# 1_Interface.net
KiCad netlist of a schematic drawn in Altium Designer
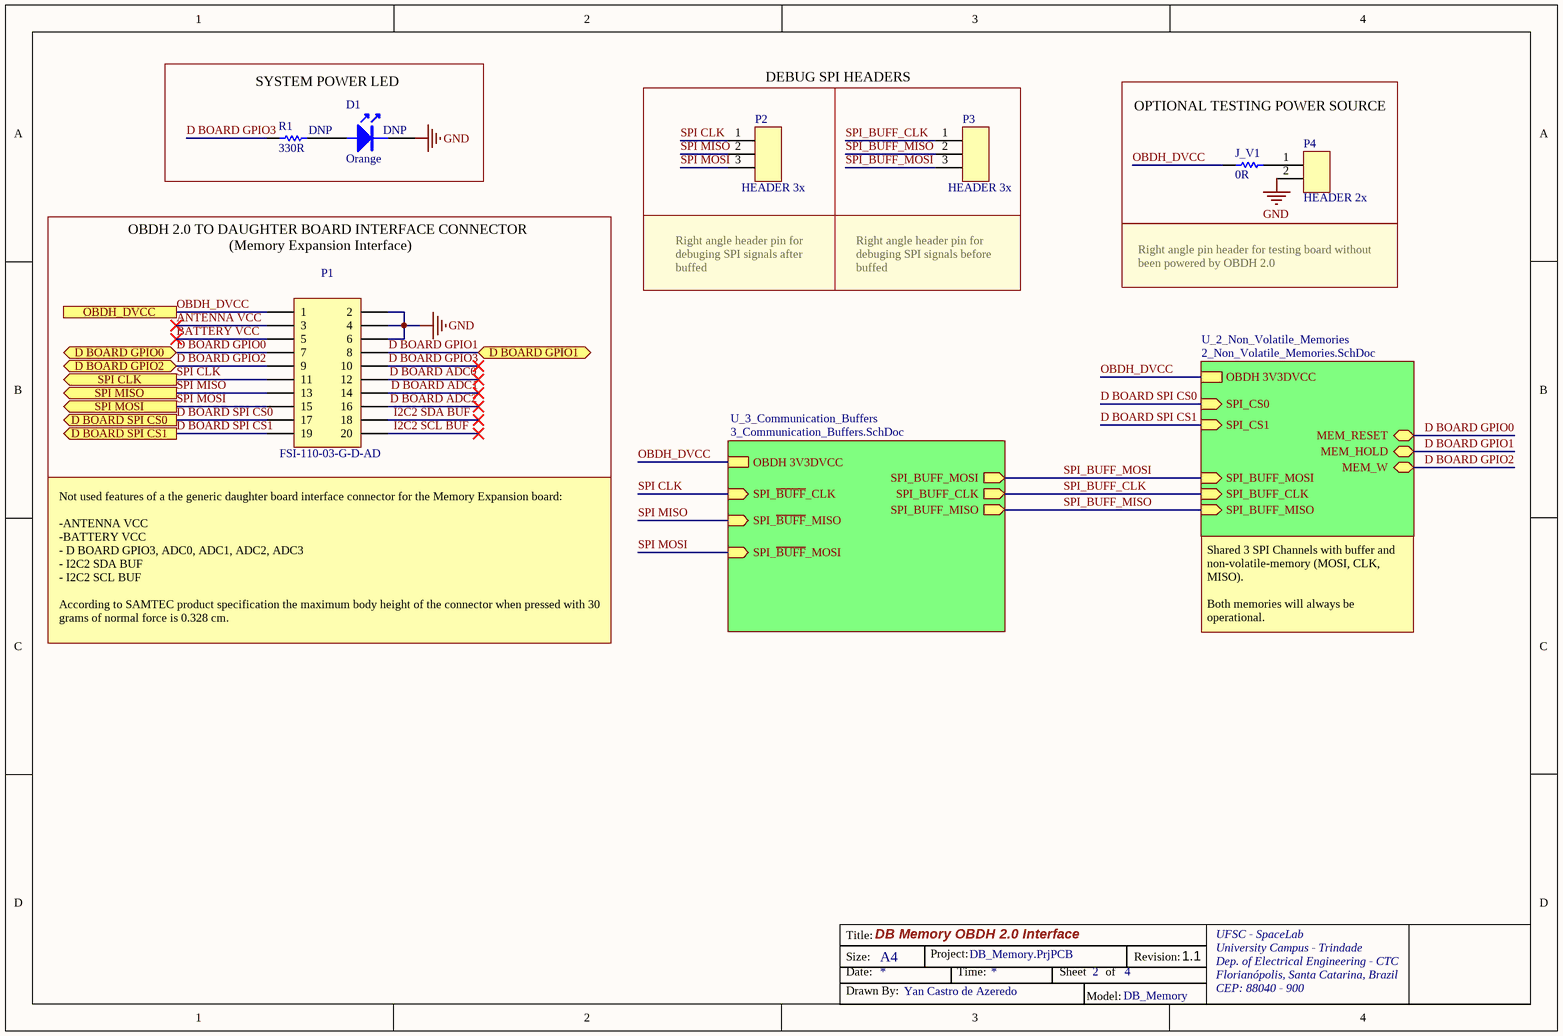
[diagram p0: 1_Interface.SchDoc]

(export (version "E")
  (design (tool "Eeschema 10.0.6"))
  (components
    (comp (ref "D1")
      (value "Orange")
      (footprint "0805-LED")
      (description "SMD Orange LED")
      (fields (field (name "PARTNUMBER") "LTST-C170KFKT") (field (name "MANUFACTURER") "Vishay Lite-On"))
      (libsource (lib "Memory_Expansion_Daughter_Board_SchLib") (part "LED/O_0802"))
    )
    (comp (ref "J_V1")
      (value "0R")
      (footprint "0805")
      (description "RES 0R OHM 1/8W JUMPER 0805")
      (fields (field (name "PARTNUMBER") "CRCW08050000Z0EA") (field (name "MANUFACTURER") "Yageo"))
      (libsource (lib "Memory_Expansion_Daughter_Board_SchLib") (part "RC0805JR-070RL"))
    )
    (comp (ref "P1")
      (value "FSI-110-03-G-D-AD")
      (footprint "Mating FSI-110-03-G-D-AD")
      (description "CONN STACKING 20POS SMD GOLD")
      (fields (field (name "MANUFACTURER") "Samtec"))
      (libsource (lib "Memory_Expansion_Daughter_Board_SchLib") (part "FSI-110-03-G-D-AD"))
    )
    (comp (ref "P2")
      (value "HEADER 3x")
      (footprint "Header1x3")
      (description "Conn Unshrouded Header HDR 3 POS 2.54mm Solder RA Thru-Hole Automotive Bulk")
      (fields
        (field (name "MANUFACTURER") "Samtec")
        (field (name "MANUFACTURER PART NUMBER") "TSW-103-08-G-S-RA")
      )
      (libsource (lib "Memory_Expansion_Daughter_Board_SchLib") (part "HEADER 3x"))
    )
    (comp (ref "P3")
      (value "HEADER 3x")
      (footprint "Header1x3")
      (description "Conn Unshrouded Header HDR 3 POS 2.54mm Solder RA Thru-Hole Automotive Bulk")
      (fields
        (field (name "MANUFACTURER") "Samtec")
        (field (name "MANUFACTURER PART NUMBER") "TSW-103-08-G-S-RA")
      )
      (libsource (lib "Memory_Expansion_Daughter_Board_SchLib") (part "HEADER 3x"))
    )
    (comp (ref "P4")
      (value "HEADER 2x")
      (footprint "HEADER 1X2")
      (description "Conn Unshrouded Header HDR 2 POS 2.54mm Solder RA Thru-Hole Automotive Bulk")
      (fields
        (field (name "MANUFACTURER") "Samtec")
        (field (name "MANUFACTURER PART NUMBER") "TSW-102-08-G-S-RA")
      )
      (libsource (lib "Memory_Expansion_Daughter_Board_SchLib") (part "HEADER 2x"))
    )
    (comp (ref "R1")
      (value "330R")
      (footprint "0805")
      (description "RES 330R OHM 1/4W 1% 0805")
      (fields (field (name "PARTNUMBER") "RC0805FR-07330RL") (field (name "MANUFACTURER") "KOA Speer"))
      (libsource (lib "Memory_Expansion_Daughter_Board_SchLib") (part "R330R_1%_1/4W_0805"))
    )
  )
  (nets
    (net (code "1") (name "/ANTENNA VCC") (class "Default")
      (node (ref "P1") (pin "3") (pinfunction "3_3") (pintype "passive+no_connect"))
    )
    (net (code "2") (name "/BATTERY VCC") (class "Default")
      (node (ref "P1") (pin "5") (pinfunction "5_5") (pintype "passive+no_connect"))
    )
    (net (code "3") (name "/D BOARD ADC0") (class "Default")
      (node (ref "P1") (pin "12") (pinfunction "12_12") (pintype "passive+no_connect"))
    )
    (net (code "4") (name "/D BOARD ADC1") (class "Default")
      (node (ref "P1") (pin "14") (pinfunction "14_14") (pintype "passive+no_connect"))
    )
    (net (code "5") (name "/D BOARD ADC2") (class "Default")
      (node (ref "P1") (pin "16") (pinfunction "16_16") (pintype "passive+no_connect"))
    )
    (net (code "6") (name "/D BOARD GPIO0") (class "Default")
      (node (ref "P1") (pin "7") (pinfunction "7_7") (pintype "passive"))
    )
    (net (code "7") (name "/D BOARD GPIO1") (class "Default")
      (node (ref "P1") (pin "8") (pinfunction "8_8") (pintype "passive"))
    )
    (net (code "8") (name "/D BOARD GPIO2") (class "Default")
      (node (ref "P1") (pin "9") (pinfunction "9_9") (pintype "passive"))
    )
    (net (code "9") (name "/D BOARD GPIO3") (class "Default")
      (node (ref "P1") (pin "10") (pinfunction "10_10") (pintype "passive"))
      (node (ref "R1") (pin "1") (pinfunction "1_1") (pintype "passive"))
    )
    (net (code "10") (name "/D BOARD SPI CS0") (class "Default")
      (node (ref "P1") (pin "17") (pinfunction "17_17") (pintype "passive"))
    )
    (net (code "11") (name "/D BOARD SPI CS1") (class "Default")
      (node (ref "P1") (pin "19") (pinfunction "19_19") (pintype "passive"))
    )
    (net (code "12") (name "/I2C2 SCL BUF") (class "Default")
      (node (ref "P1") (pin "20") (pinfunction "20_20") (pintype "passive+no_connect"))
    )
    (net (code "13") (name "/I2C2 SDA BUF") (class "Default")
      (node (ref "P1") (pin "18") (pinfunction "18_18") (pintype "passive+no_connect"))
    )
    (net (code "14") (name "/OBDH_DVCC") (class "Default")
      (node (ref "J_V1") (pin "2") (pinfunction "2_2") (pintype "passive"))
      (node (ref "P1") (pin "1") (pinfunction "1_1") (pintype "passive"))
    )
    (net (code "15") (name "/SPI CLK") (class "Default")
      (node (ref "P1") (pin "11") (pinfunction "11_11") (pintype "passive"))
      (node (ref "P2") (pin "1") (pintype "passive"))
    )
    (net (code "16") (name "/SPI MISO") (class "Default")
      (node (ref "P1") (pin "13") (pinfunction "13_13") (pintype "passive"))
      (node (ref "P2") (pin "2") (pintype "passive"))
    )
    (net (code "17") (name "/SPI MOSI") (class "Default")
      (node (ref "P1") (pin "15") (pinfunction "15_15") (pintype "passive"))
      (node (ref "P2") (pin "3") (pintype "passive"))
    )
    (net (code "18") (name "/SPI_BUFF_CLK") (class "Default") (node (ref "P3") (pin "1") (pintype "passive")))
    (net (code "20") (name "/SPI_BUFF_MISO") (class "Default")
      (node (ref "P3") (pin "2") (pintype "passive"))
    )
    (net (code "22") (name "/SPI_BUFF_MOSI") (class "Default")
      (node (ref "P3") (pin "3") (pintype "passive"))
    )
    (net (code "24") (name "GND") (class "Default")
      (node (ref "D1") (pin "2") (pinfunction "K_2") (pintype "passive"))
      (node (ref "P1") (pin "2") (pinfunction "2_2") (pintype "passive"))
      (node (ref "P1") (pin "4") (pinfunction "4_4") (pintype "passive"))
      (node (ref "P1") (pin "6") (pinfunction "6_6") (pintype "passive"))
      (node (ref "P4") (pin "2") (pintype "passive"))
    )
    (net (code "25") (name "Net-(D1-A)") (class "Default")
      (node (ref "D1") (pin "1") (pinfunction "A_1") (pintype "passive"))
      (node (ref "R1") (pin "2") (pinfunction "2_2") (pintype "passive"))
    )
    (net (code "26") (name "Net-(J_V1-Pad1)") (class "Default")
      (node (ref "J_V1") (pin "1") (pinfunction "1_1") (pintype "passive"))
      (node (ref "P4") (pin "1") (pintype "passive"))
    )
  )
)
